# programming.net
KiCad netlist of a schematic drawn in Altium Designer
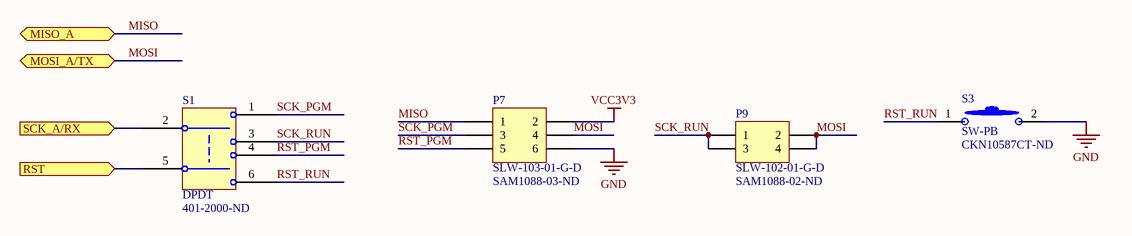
[diagram p0: programming.SchDoc]

(export (version "E")
  (design (tool "Eeschema 10.0.6"))
  (components
    (comp (ref "P7")
      (value "SLW-103-01-G-D")
      (footprint "SLW-103-01-X-D")
      (description "6 pos 100mil pitch low profile header")
      (fields (field (name "SUPPLIER PART NUMBER 1") "SAM1088-03-ND"))
      (libsource (lib "heron-general") (part "SLW-103-01-G-D"))
    )
    (comp (ref "P9")
      (value "SLW-102-01-G-D")
      (footprint "SLW-102-01-X-D")
      (description "4 pos 100mil pitch low profile header")
      (fields (field (name "SUPPLIER PART NUMBER 1") "SAM1088-02-ND"))
      (libsource (lib "heron-general") (part "SLW-102-01-G-D"))
    )
    (comp (ref "S1")
      (value "DPDT")
      (footprint "JS202011AQN - Slide Switch")
      (description "DPDT Switch, customized for the pinout of the JS202011AQN switch.")
      (fields (field (name "SUPPLIER PART NUMBER 1") "401-2000-ND"))
      (libsource (lib "heron-general") (part "DPDT Switch"))
    )
    (comp (ref "S3")
      (value "SW-PB")
      (footprint "PTS830GM140 SMTR LFS - Pushbutton")
      (description "Schematic symbol for a generic 2-pin pushbutton, OFF-mom.")
      (fields (field (name "SUPPLIER PART NUMBER 1") "CKN10587CT-ND"))
      (libsource (lib "heron-general") (part "Pushbutton - Low Profile"))
    )
  )
  (nets
    (net (code "1") (name "/MISO") (class "Default")
      (node (ref "P7") (pin "1") (pinfunction "1_1") (pintype "passive"))
    )
    (net (code "2") (name "/MOSI") (class "Default")
      (node (ref "P7") (pin "4") (pinfunction "4_4") (pintype "passive"))
      (node (ref "P9") (pin "2") (pinfunction "2_2") (pintype "passive"))
      (node (ref "P9") (pin "4") (pinfunction "4_4") (pintype "passive"))
    )
    (net (code "3") (name "/RST") (class "Default")
      (node (ref "S1") (pin "5") (pinfunction "POLE2_5") (pintype "passive"))
    )
    (net (code "4") (name "/RST_PGM") (class "Default")
      (node (ref "P7") (pin "5") (pinfunction "5_5") (pintype "passive"))
      (node (ref "S1") (pin "4") (pinfunction "POLE2A_4") (pintype "passive"))
    )
    (net (code "5") (name "/RST_RUN") (class "Default")
      (node (ref "S1") (pin "6") (pinfunction "POLE2B_6") (pintype "passive"))
      (node (ref "S3") (pin "1") (pinfunction "1_1") (pintype "passive"))
    )
    (net (code "6") (name "/SCK_A{slash}RX") (class "Default")
      (node (ref "S1") (pin "2") (pinfunction "POLE1_2") (pintype "passive"))
    )
    (net (code "7") (name "/SCK_PGM") (class "Default")
      (node (ref "P7") (pin "3") (pinfunction "3_3") (pintype "passive"))
      (node (ref "S1") (pin "1") (pinfunction "POLE1A_1") (pintype "passive"))
    )
    (net (code "8") (name "/SCK_RUN") (class "Default")
      (node (ref "P9") (pin "1") (pinfunction "1_1") (pintype "passive"))
      (node (ref "P9") (pin "3") (pinfunction "3_3") (pintype "passive"))
      (node (ref "S1") (pin "3") (pinfunction "POLE1B_3") (pintype "passive"))
    )
    (net (code "9") (name "GND") (class "Default")
      (node (ref "P7") (pin "6") (pinfunction "6_6") (pintype "passive"))
      (node (ref "S3") (pin "2") (pinfunction "2_2") (pintype "passive"))
    )
    (net (code "10") (name "VCC3V3") (class "Default")
      (node (ref "P7") (pin "2") (pinfunction "2_2") (pintype "passive"))
    )
  )
)
